# system.net
KiCad netlist of a schematic drawn in Altium Designer
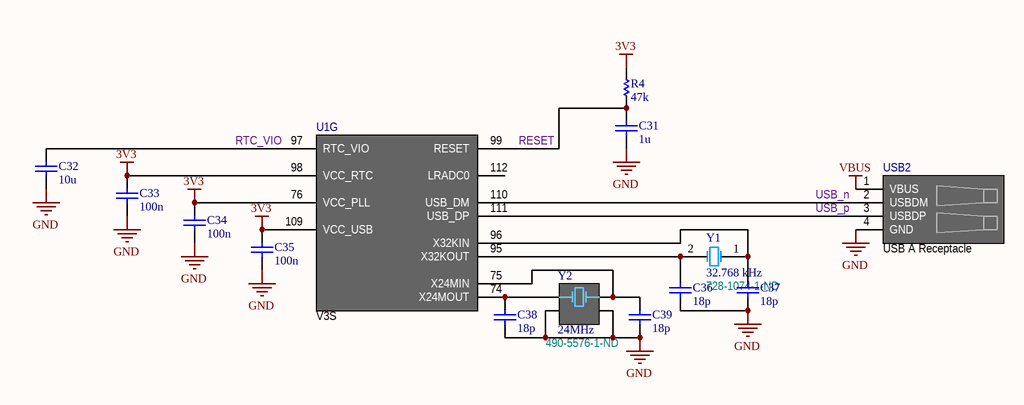
[diagram p0: system.SchDoc]

(export (version "E")
  (design (tool "Eeschema 10.0.6"))
  (components
    (comp (ref "C31")
      (value "1u")
      (footprint "CAPC1005N")
      (description "Capacitor (Semiconductor SIM Model)")
      (fields (field (name "PUBLISHER") "Altium Limited"))
      (libsource (lib "Miscellaneous Devices") (part "Cap Semi"))
    )
    (comp (ref "C32")
      (value "10u")
      (footprint "CAPC1608N")
      (description "Capacitor (Semiconductor SIM Model)")
      (fields (field (name "PUBLISHER") "Altium Limited"))
      (libsource (lib "Miscellaneous Devices") (part "Cap Semi"))
    )
    (comp (ref "C33")
      (value "100n")
      (footprint "CAPC1005N")
      (description "Capacitor (Semiconductor SIM Model)")
      (fields (field (name "PUBLISHER") "Altium Limited"))
      (libsource (lib "Miscellaneous Devices") (part "Cap Semi"))
    )
    (comp (ref "C34")
      (value "100n")
      (footprint "CAPC1005N")
      (description "Capacitor (Semiconductor SIM Model)")
      (fields (field (name "PUBLISHER") "Altium Limited"))
      (libsource (lib "Miscellaneous Devices") (part "Cap Semi"))
    )
    (comp (ref "C35")
      (value "100n")
      (footprint "CAPC1005N")
      (description "Capacitor (Semiconductor SIM Model)")
      (fields (field (name "PUBLISHER") "Altium Limited"))
      (libsource (lib "Miscellaneous Devices") (part "Cap Semi"))
    )
    (comp (ref "C36")
      (value "18p")
      (footprint "CAPC1005N")
      (description "Capacitor (Semiconductor SIM Model)")
      (fields (field (name "PUBLISHER") "Altium Limited"))
      (libsource (lib "Miscellaneous Devices") (part "Cap Semi"))
    )
    (comp (ref "C37")
      (value "18p")
      (footprint "CAPC1005N")
      (description "Capacitor (Semiconductor SIM Model)")
      (fields (field (name "PUBLISHER") "Altium Limited"))
      (libsource (lib "Miscellaneous Devices") (part "Cap Semi"))
    )
    (comp (ref "C38")
      (value "18p")
      (footprint "CAPC1005N")
      (description "Capacitor (Semiconductor SIM Model)")
      (fields (field (name "PUBLISHER") "Altium Limited"))
      (libsource (lib "Miscellaneous Devices") (part "Cap Semi"))
    )
    (comp (ref "C39")
      (value "18p")
      (footprint "CAPC1005N")
      (description "Capacitor (Semiconductor SIM Model)")
      (fields (field (name "PUBLISHER") "Altium Limited"))
      (libsource (lib "Miscellaneous Devices") (part "Cap Semi"))
    )
    (comp (ref "R4")
      (value "47k")
      (footprint "RESC1005N")
      (description "Semiconductor Resistor")
      (fields (field (name "PUBLISHER") "Altium Limited"))
      (libsource (lib "Miscellaneous Devices") (part "Res Semi"))
    )
    (comp (ref "U1") (value "V3S") (footprint "V3S") (libsource (lib "Allwinner SoC") (part "V3S")))
    (comp (ref "USB2")
      (value "USB A Receptacle")
      (footprint "USB2.0-4H4")
      (libsource (lib "Miscellaneous Connectors") (part "USB A Receptacle"))
    )
    (comp (ref "Y1")
      (value "32.768 kHz")
      (footprint "ABS07")
      (description "Crystal Oscillator (2 pin)")
      (fields
        (field (name "SUPPLIER PART NUMBER 1") "728-1074-1-ND")
        (field (name "PUBLISHER") "Altium Limited")
      )
      (libsource (lib "Miscellaneous Devices") (part "XTAL"))
    )
    (comp (ref "Y2")
      (value "24MHz")
      (footprint "XTAL3225-4-N")
      (description "Crystal Oscillator (4 pin)")
      (fields
        (field (name "SUPPLIER PART NUMBER 1") "490-5576-1-ND")
        (field (name "PUBLISHER") "Altium Limited")
      )
      (libsource (lib "Miscellaneous Devices") (part "XTAL_4SMD"))
    )
  )
  (nets
    (net (code "1") (name "/RESET") (class "Default")
      (node (ref "C31") (pin "2") (pinfunction "2_2") (pintype "passive"))
      (node (ref "R4") (pin "1") (pinfunction "1_1") (pintype "passive"))
      (node (ref "U1") (pin "99") (pinfunction "RESET_99") (pintype "passive"))
    )
    (net (code "2") (name "/RTC_VIO") (class "Default")
      (node (ref "C32") (pin "2") (pinfunction "2_2") (pintype "passive"))
      (node (ref "U1") (pin "97") (pinfunction "RTC_VIO_97") (pintype "passive"))
    )
    (net (code "3") (name "/USB_n") (class "Default")
      (node (ref "U1") (pin "110") (pinfunction "USB_DM_110") (pintype "passive"))
      (node (ref "USB2") (pin "2") (pinfunction "USBDM_2") (pintype "power_in"))
    )
    (net (code "4") (name "/USB_p") (class "Default")
      (node (ref "U1") (pin "111") (pinfunction "USB_DP_111") (pintype "passive"))
      (node (ref "USB2") (pin "3") (pinfunction "USBDP_3") (pintype "power_in"))
    )
    (net (code "5") (name "3V3") (class "Default")
      (node (ref "C33") (pin "2") (pinfunction "2_2") (pintype "passive"))
      (node (ref "C34") (pin "2") (pinfunction "2_2") (pintype "passive"))
      (node (ref "C35") (pin "2") (pinfunction "2_2") (pintype "passive"))
      (node (ref "R4") (pin "2") (pinfunction "2_2") (pintype "passive"))
      (node (ref "U1") (pin "109") (pinfunction "VCC_USB_109") (pintype "passive"))
      (node (ref "U1") (pin "76") (pinfunction "VCC_PLL_76") (pintype "passive"))
      (node (ref "U1") (pin "98") (pinfunction "VCC_RTC_98") (pintype "passive"))
    )
    (net (code "6") (name "GND") (class "Default")
      (node (ref "C31") (pin "1") (pinfunction "1_1") (pintype "passive"))
      (node (ref "C32") (pin "1") (pinfunction "1_1") (pintype "passive"))
      (node (ref "C33") (pin "1") (pinfunction "1_1") (pintype "passive"))
      (node (ref "C34") (pin "1") (pinfunction "1_1") (pintype "passive"))
      (node (ref "C35") (pin "1") (pinfunction "1_1") (pintype "passive"))
      (node (ref "C36") (pin "1") (pinfunction "1_1") (pintype "passive"))
      (node (ref "C37") (pin "1") (pinfunction "1_1") (pintype "passive"))
      (node (ref "C38") (pin "1") (pinfunction "1_1") (pintype "passive"))
      (node (ref "C39") (pin "1") (pinfunction "1_1") (pintype "passive"))
      (node (ref "USB2") (pin "4") (pinfunction "GND_4") (pintype "power_in"))
      (node (ref "Y2") (pin "2") (pinfunction "2_2") (pintype "power_in"))
      (node (ref "Y2") (pin "4") (pinfunction "4_4") (pintype "power_in"))
    )
    (net (code "7") (name "Net-(U1G-X24MIN)") (class "Default")
      (node (ref "C39") (pin "2") (pinfunction "2_2") (pintype "passive"))
      (node (ref "U1") (pin "75") (pinfunction "X24MIN_75") (pintype "passive"))
      (node (ref "Y2") (pin "3") (pinfunction "OSC2_3") (pintype "passive"))
    )
    (net (code "8") (name "Net-(U1G-X24MOUT)") (class "Default")
      (node (ref "C38") (pin "2") (pinfunction "2_2") (pintype "passive"))
      (node (ref "U1") (pin "74") (pinfunction "X24MOUT_74") (pintype "passive"))
      (node (ref "Y2") (pin "1") (pinfunction "OSC1_1") (pintype "passive"))
    )
    (net (code "9") (name "Net-(U1G-X32KIN)") (class "Default")
      (node (ref "C37") (pin "2") (pinfunction "2_2") (pintype "passive"))
      (node (ref "U1") (pin "96") (pinfunction "X32KIN_96") (pintype "passive"))
      (node (ref "Y1") (pin "1") (pinfunction "OSC1_1") (pintype "passive"))
    )
    (net (code "10") (name "Net-(U1G-X32KOUT)") (class "Default")
      (node (ref "C36") (pin "2") (pinfunction "2_2") (pintype "passive"))
      (node (ref "U1") (pin "95") (pinfunction "X32KOUT_95") (pintype "passive"))
      (node (ref "Y1") (pin "2") (pinfunction "OSC2_2") (pintype "passive"))
    )
    (net (code "11") (name "VBUS") (class "Default")
      (node (ref "USB2") (pin "1") (pinfunction "VBUS_1") (pintype "power_in"))
    )
    (net (code "12") (name "unconnected-(U1G-LRADC0-Pad112)") (class "Default")
      (node (ref "U1") (pin "112") (pinfunction "LRADC0_112") (pintype "passive"))
    )
  )
)
